# Electronic_Design.net
KiCad netlist of a schematic drawn in EAGLE
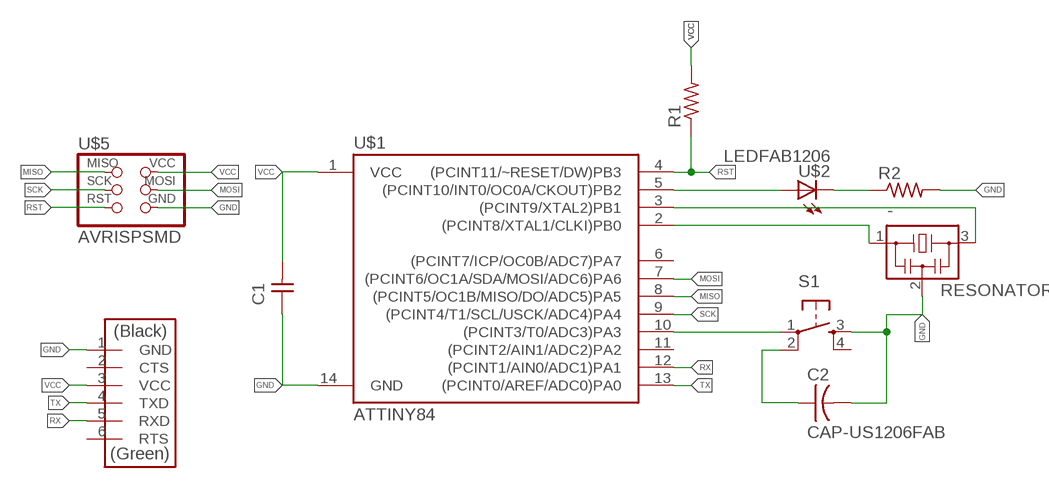
[diagram p0: schematic, sheet 1]

(export (version "E")
  (design (tool "Eeschema 10.0.6"))
  (components
    (comp (ref "-")
      (value "RESONATOR")
      (footprint "eagle-import:EFOBM")
      (libsource (lib "eagle-import") (part "RESONATOR"))
    )
    (comp (ref "C1")
      (value "CAP-UNPOLARIZEDFAB")
      (footprint "eagle-import:C1206FAB")
      (libsource (lib "eagle-import") (part "CAP-UNPOLARIZEDFAB"))
    )
    (comp (ref "C2")
      (value "CAP-US1206FAB")
      (footprint "eagle-import:C1206FAB")
      (libsource (lib "eagle-import") (part "CAP-US1206FAB"))
    )
    (comp (ref "R1")
      (value "RES-US1206FAB")
      (footprint "eagle-import:R1206FAB")
      (libsource (lib "eagle-import") (part "RES-US1206FAB"))
    )
    (comp (ref "R2")
      (value "RES-US1206FAB")
      (footprint "eagle-import:R1206FAB")
      (libsource (lib "eagle-import") (part "RES-US1206FAB"))
    )
    (comp (ref "S1")
      (value "6MM_SWITCH6MM_SWITCH")
      (footprint "eagle-import:6MM_SWITCH")
      (libsource (lib "eagle-import") (part "6MM_SWITCH6MM_SWITCH"))
    )
    (comp (ref "U$1")
      (value "ATTINY84")
      (footprint "eagle-import:SO14")
      (libsource (lib "eagle-import") (part "ATTINY84"))
    )
    (comp (ref "U$2")
      (value "LEDFAB1206")
      (footprint "eagle-import:LED1206FAB")
      (libsource (lib "eagle-import") (part "LEDFAB1206"))
    )
    (comp (ref "U$3")
      (value "FTDI-SMD-HEADER")
      (footprint "eagle-import:1X06SMD")
      (libsource (lib "eagle-import") (part "FTDI-SMD-HEADER"))
    )
    (comp (ref "U$5")
      (value "AVRISPSMD")
      (footprint "eagle-import:2X03SMD")
      (libsource (lib "eagle-import") (part "AVRISPSMD"))
    )
  )
  (nets
    (net (code "1") (name "GND") (class "Default")
      (node (ref "-") (pin "2") (pinfunction "2_2") (pintype "passive"))
      (node (ref "C1") (pin "1") (pinfunction "1_1") (pintype "passive"))
      (node (ref "C2") (pin "2") (pinfunction "2_2") (pintype "passive"))
      (node (ref "R2") (pin "2") (pinfunction "2_2") (pintype "passive"))
      (node (ref "S1") (pin "3") (pinfunction "S_3") (pintype "passive"))
      (node (ref "U$1") (pin "14") (pinfunction "GND_14") (pintype "bidirectional"))
      (node (ref "U$3") (pin "1") (pinfunction "GND_1") (pintype "bidirectional"))
      (node (ref "U$5") (pin "6") (pinfunction "GND_6") (pintype "passive"))
    )
    (net (code "2") (name "MISO") (class "Default")
      (node (ref "U$1") (pin "8") (pinfunction "(PCINT5/OC1B/MISO/DO/ADC5)PA5_8") (pintype "bidirectional"))
      (node (ref "U$5") (pin "1") (pinfunction "MISO_1") (pintype "passive"))
    )
    (net (code "3") (name "MOSI") (class "Default")
      (node (ref "U$1") (pin "7") (pinfunction "(PCINT6/OC1A/SDA/MOSI/ADC6)PA6_7") (pintype "bidirectional"))
      (node (ref "U$5") (pin "4") (pinfunction "MOSI_4") (pintype "passive"))
    )
    (net (code "4") (name "Net-(S1-P)") (class "Default")
      (node (ref "S1") (pin "1") (pinfunction "P_1") (pintype "passive"))
      (node (ref "U$1") (pin "10") (pinfunction "(PCINT3/T0/ADC3)PA3_10") (pintype "bidirectional"))
    )
    (net (code "5") (name "Net-(S1-P1)") (class "Default")
      (node (ref "C2") (pin "1") (pinfunction "1_1") (pintype "passive"))
      (node (ref "S1") (pin "2") (pinfunction "P1_2") (pintype "passive"))
    )
    (net (code "6") (name "Net-(U$1-(PCINT8{slash}XTAL1{slash}CLKI)PB0)") (class "Default")
      (node (ref "-") (pin "1") (pinfunction "1_1") (pintype "passive"))
      (node (ref "U$1") (pin "2") (pinfunction "(PCINT8/XTAL1/CLKI)PB0_2") (pintype "bidirectional"))
    )
    (net (code "7") (name "Net-(U$1-(PCINT9{slash}XTAL2)PB1)") (class "Default")
      (node (ref "-") (pin "3") (pinfunction "3_3") (pintype "passive"))
      (node (ref "U$1") (pin "3") (pinfunction "(PCINT9/XTAL2)PB1_3") (pintype "bidirectional"))
    )
    (net (code "8") (name "Net-(U$1-(PCINT10{slash}INT0{slash}OC0A{slash}CKOUT)PB2)") (class "Default")
      (node (ref "U$1") (pin "5") (pinfunction "(PCINT10/INT0/OC0A/CKOUT)PB2_5") (pintype "bidirectional"))
      (node (ref "U$2") (pin "1") (pinfunction "A_1") (pintype "passive"))
    )
    (net (code "9") (name "Net-(U$2-C)") (class "Default")
      (node (ref "R2") (pin "1") (pinfunction "1_1") (pintype "passive"))
      (node (ref "U$2") (pin "2") (pinfunction "C_2") (pintype "passive"))
    )
    (net (code "10") (name "RST") (class "Default")
      (node (ref "R1") (pin "1") (pinfunction "1_1") (pintype "passive"))
      (node (ref "U$1") (pin "4") (pinfunction "(PCINT11/~{RESET/DW})PB3_4") (pintype "bidirectional"))
      (node (ref "U$5") (pin "5") (pinfunction "RST_5") (pintype "passive"))
    )
    (net (code "11") (name "RX") (class "Default")
      (node (ref "U$1") (pin "12") (pinfunction "(PCINT1/AIN0/ADC1)PA1_12") (pintype "bidirectional"))
      (node (ref "U$3") (pin "5") (pinfunction "RXD_5") (pintype "bidirectional"))
    )
    (net (code "12") (name "SCK") (class "Default")
      (node (ref "U$1") (pin "9") (pinfunction "(PCINT4/T1/SCL/USCK/ADC4)PA4_9") (pintype "bidirectional"))
      (node (ref "U$5") (pin "3") (pinfunction "SCK_3") (pintype "passive"))
    )
    (net (code "13") (name "TX") (class "Default")
      (node (ref "U$1") (pin "13") (pinfunction "(PCINT0/AREF/ADC0)PA0_13") (pintype "bidirectional"))
      (node (ref "U$3") (pin "4") (pinfunction "TXD_4") (pintype "bidirectional"))
    )
    (net (code "14") (name "VCC") (class "Default")
      (node (ref "C1") (pin "2") (pinfunction "2_2") (pintype "passive"))
      (node (ref "R1") (pin "2") (pinfunction "2_2") (pintype "passive"))
      (node (ref "U$1") (pin "1") (pinfunction "VCC_1") (pintype "bidirectional"))
      (node (ref "U$3") (pin "3") (pinfunction "VCC_3") (pintype "bidirectional"))
      (node (ref "U$5") (pin "2") (pinfunction "VCC_2") (pintype "passive"))
    )
    (net (code "15") (name "unconnected-(S1-S1-Pad4)") (class "Default")
      (node (ref "S1") (pin "4") (pinfunction "S1_4") (pintype "passive"))
    )
    (net (code "16") (name "unconnected-(U$1-(PCINT2{slash}AIN1{slash}ADC2)PA2-Pad11)") (class "Default")
      (node (ref "U$1") (pin "11") (pinfunction "(PCINT2/AIN1/ADC2)PA2_11") (pintype "bidirectional"))
    )
    (net (code "17") (name "unconnected-(U$1-(PCINT7{slash}ICP{slash}OC0B{slash}ADC7)PA7-Pad6)") (class "Default")
      (node (ref "U$1") (pin "6") (pinfunction "(PCINT7/ICP/OC0B/ADC7)PA7_6") (pintype "bidirectional"))
    )
    (net (code "18") (name "unconnected-(U$3-CTS-Pad2)") (class "Default")
      (node (ref "U$3") (pin "2") (pinfunction "CTS_2") (pintype "bidirectional"))
    )
    (net (code "19") (name "unconnected-(U$3-RTS-Pad6)") (class "Default")
      (node (ref "U$3") (pin "6") (pinfunction "RTS_6") (pintype "bidirectional"))
    )
  )
)
